# PSU_2x.net
KiCad netlist of a schematic drawn in EAGLE
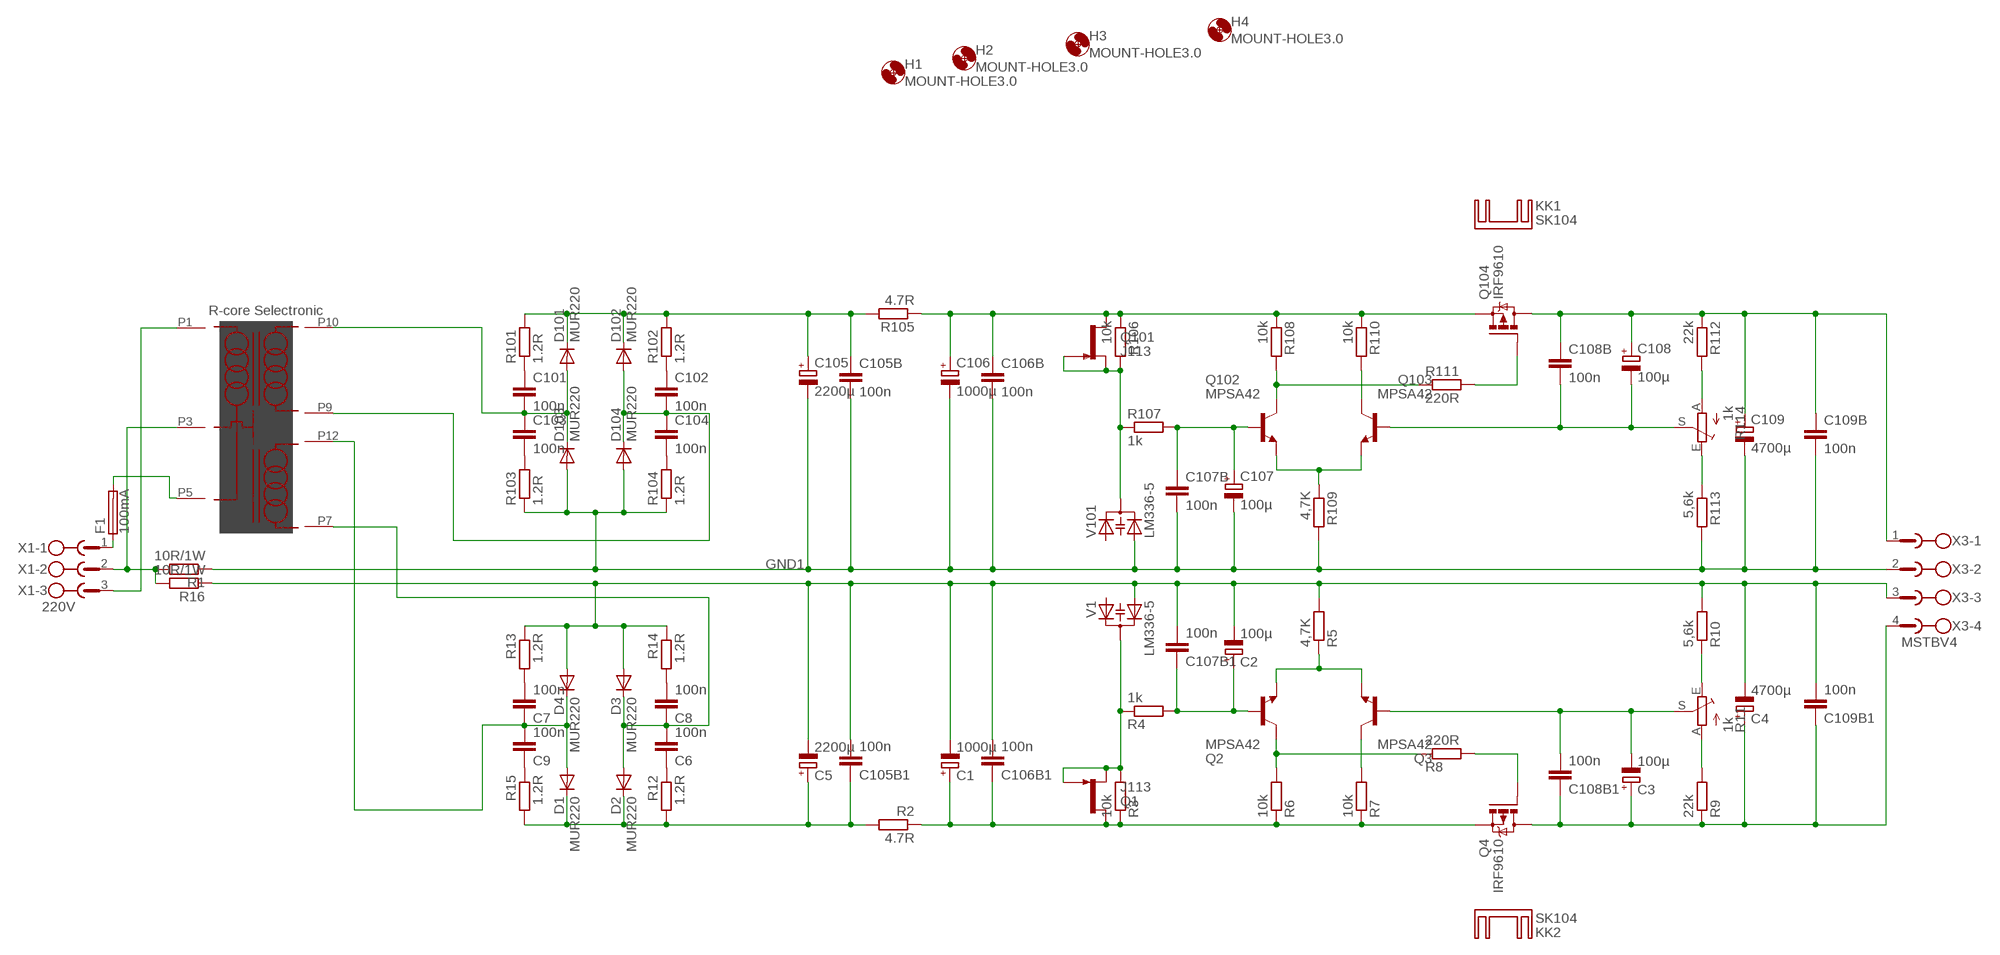
[diagram p0: schematic, sheet 1]

(export (version "E")
  (design (tool "Eeschema 10.0.6"))
  (components
    (comp (ref "C1")
      (value "1000µ")
      (footprint "eagle-import:E7,5-16")
      (libsource (lib "eagle-import") (part "CPOL-EUE7.5-16"))
    )
    (comp (ref "C2")
      (value "100µ")
      (footprint "eagle-import:E5-10,5")
      (libsource (lib "eagle-import") (part "CPOL-EUE5-10.5"))
    )
    (comp (ref "C3")
      (value "100µ")
      (footprint "eagle-import:E5-10,5")
      (libsource (lib "eagle-import") (part "CPOL-EUE5-10.5"))
    )
    (comp (ref "C4")
      (value "4700µ")
      (footprint "eagle-import:EB25D")
      (libsource (lib "eagle-import") (part "CPOL-EUE10-25"))
    )
    (comp (ref "C5")
      (value "2200µ")
      (footprint "eagle-import:E7,5-16")
      (libsource (lib "eagle-import") (part "CPOL-EUE7.5-16"))
    )
    (comp (ref "C6")
      (value "100n")
      (footprint "eagle-import:C050-025X075")
      (libsource (lib "eagle-import") (part "C-EU050-025X075"))
    )
    (comp (ref "C7")
      (value "100n")
      (footprint "eagle-import:C050-025X075")
      (libsource (lib "eagle-import") (part "C-EU050-025X075"))
    )
    (comp (ref "C8")
      (value "100n")
      (footprint "eagle-import:C050-025X075")
      (libsource (lib "eagle-import") (part "C-EU050-025X075"))
    )
    (comp (ref "C9")
      (value "100n")
      (footprint "eagle-import:C050-025X075")
      (libsource (lib "eagle-import") (part "C-EU050-025X075"))
    )
    (comp (ref "C101")
      (value "100n")
      (footprint "eagle-import:C050-025X075")
      (libsource (lib "eagle-import") (part "C-EU050-025X075"))
    )
    (comp (ref "C102")
      (value "100n")
      (footprint "eagle-import:C050-025X075")
      (libsource (lib "eagle-import") (part "C-EU050-025X075"))
    )
    (comp (ref "C103")
      (value "100n")
      (footprint "eagle-import:C050-025X075")
      (libsource (lib "eagle-import") (part "C-EU050-025X075"))
    )
    (comp (ref "C104")
      (value "100n")
      (footprint "eagle-import:C050-025X075")
      (libsource (lib "eagle-import") (part "C-EU050-025X075"))
    )
    (comp (ref "C105")
      (value "2200µ")
      (footprint "eagle-import:E7,5-16")
      (libsource (lib "eagle-import") (part "CPOL-EUE7.5-16"))
    )
    (comp (ref "C105B")
      (value "100n")
      (footprint "eagle-import:C050-025X075")
      (libsource (lib "eagle-import") (part "C-EU050-025X075"))
    )
    (comp (ref "C105B1")
      (value "100n")
      (footprint "eagle-import:C050-025X075")
      (libsource (lib "eagle-import") (part "C-EU050-025X075"))
    )
    (comp (ref "C106")
      (value "1000µ")
      (footprint "eagle-import:E7,5-16")
      (libsource (lib "eagle-import") (part "CPOL-EUE7.5-16"))
    )
    (comp (ref "C106B")
      (value "100n")
      (footprint "eagle-import:C050-025X075")
      (libsource (lib "eagle-import") (part "C-EU050-025X075"))
    )
    (comp (ref "C106B1")
      (value "100n")
      (footprint "eagle-import:C050-025X075")
      (libsource (lib "eagle-import") (part "C-EU050-025X075"))
    )
    (comp (ref "C107")
      (value "100µ")
      (footprint "eagle-import:E5-10,5")
      (libsource (lib "eagle-import") (part "CPOL-EUE5-10.5"))
    )
    (comp (ref "C107B")
      (value "100n")
      (footprint "eagle-import:C050-025X075")
      (libsource (lib "eagle-import") (part "C-EU050-025X075"))
    )
    (comp (ref "C107B1")
      (value "100n")
      (footprint "eagle-import:C050-025X075")
      (libsource (lib "eagle-import") (part "C-EU050-025X075"))
    )
    (comp (ref "C108")
      (value "100µ")
      (footprint "eagle-import:E5-10,5")
      (libsource (lib "eagle-import") (part "CPOL-EUE5-10.5"))
    )
    (comp (ref "C108B")
      (value "100n")
      (footprint "eagle-import:C050-025X075")
      (libsource (lib "eagle-import") (part "C-EU050-025X075"))
    )
    (comp (ref "C108B1")
      (value "100n")
      (footprint "eagle-import:C050-025X075")
      (libsource (lib "eagle-import") (part "C-EU050-025X075"))
    )
    (comp (ref "C109")
      (value "4700µ")
      (footprint "eagle-import:EB25D")
      (libsource (lib "eagle-import") (part "CPOL-EUE10-25"))
    )
    (comp (ref "C109B")
      (value "100n")
      (footprint "eagle-import:C050-025X075")
      (libsource (lib "eagle-import") (part "C-EU050-025X075"))
    )
    (comp (ref "C109B1")
      (value "100n")
      (footprint "eagle-import:C050-025X075")
      (libsource (lib "eagle-import") (part "C-EU050-025X075"))
    )
    (comp (ref "D1")
      (value "MUR220")
      (footprint "eagle-import:DO201-15")
      (libsource (lib "eagle-import") (part "BY500"))
    )
    (comp (ref "D2")
      (value "MUR220")
      (footprint "eagle-import:DO201-15")
      (libsource (lib "eagle-import") (part "BY500"))
    )
    (comp (ref "D3")
      (value "MUR220")
      (footprint "eagle-import:DO201-15")
      (libsource (lib "eagle-import") (part "BY500"))
    )
    (comp (ref "D4")
      (value "MUR220")
      (footprint "eagle-import:DO201-15")
      (libsource (lib "eagle-import") (part "BY500"))
    )
    (comp (ref "D101")
      (value "MUR220")
      (footprint "eagle-import:DO201-15")
      (libsource (lib "eagle-import") (part "BY500"))
    )
    (comp (ref "D102")
      (value "MUR220")
      (footprint "eagle-import:DO201-15")
      (libsource (lib "eagle-import") (part "BY500"))
    )
    (comp (ref "D103")
      (value "MUR220")
      (footprint "eagle-import:DO201-15")
      (libsource (lib "eagle-import") (part "BY500"))
    )
    (comp (ref "D104")
      (value "MUR220")
      (footprint "eagle-import:DO201-15")
      (libsource (lib "eagle-import") (part "BY500"))
    )
    (comp (ref "F1")
      (value "100mA")
      (footprint "eagle-import:GSH15")
      (fields (field (name "MPN") "64900001039"))
      (libsource (lib "eagle-import") (part "GSH15"))
    )
    (comp (ref "H1")
      (value "MOUNT-HOLE3.0")
      (footprint "eagle-import:3,0")
      (libsource (lib "eagle-import") (part "MOUNT-HOLE3.0"))
    )
    (comp (ref "H2")
      (value "MOUNT-HOLE3.0")
      (footprint "eagle-import:3,0")
      (libsource (lib "eagle-import") (part "MOUNT-HOLE3.0"))
    )
    (comp (ref "H3")
      (value "MOUNT-HOLE3.0")
      (footprint "eagle-import:3,0")
      (libsource (lib "eagle-import") (part "MOUNT-HOLE3.0"))
    )
    (comp (ref "H4")
      (value "MOUNT-HOLE3.0")
      (footprint "eagle-import:3,0")
      (libsource (lib "eagle-import") (part "MOUNT-HOLE3.0"))
    )
    (comp (ref "KK1")
      (value "SK104")
      (footprint "eagle-import:SK104")
      (libsource (lib "eagle-import") (part "SK104"))
    )
    (comp (ref "KK2")
      (value "SK104")
      (footprint "eagle-import:SK104")
      (libsource (lib "eagle-import") (part "SK104"))
    )
    (comp (ref "Q1")
      (value "J113")
      (footprint "eagle-import:TO-92")
      (libsource (lib "eagle-import") (part "2N5458"))
    )
    (comp (ref "Q2")
      (value "MPSA42")
      (footprint "eagle-import:TO92-EBC")
      (libsource (lib "eagle-import") (part "-NPN-TO92-EBC"))
    )
    (comp (ref "Q3")
      (value "MPSA42")
      (footprint "eagle-import:TO92-EBC")
      (libsource (lib "eagle-import") (part "-NPN-TO92-EBC"))
    )
    (comp (ref "Q4")
      (value "IRF9610")
      (footprint "eagle-import:TO220BV")
      (libsource (lib "eagle-import") (part "IRF9530"))
    )
    (comp (ref "Q101")
      (value "J113")
      (footprint "eagle-import:TO-92")
      (libsource (lib "eagle-import") (part "2N5458"))
    )
    (comp (ref "Q102")
      (value "MPSA42")
      (footprint "eagle-import:TO92-EBC")
      (libsource (lib "eagle-import") (part "-NPN-TO92-EBC"))
    )
    (comp (ref "Q103")
      (value "MPSA42")
      (footprint "eagle-import:TO92-EBC")
      (libsource (lib "eagle-import") (part "-NPN-TO92-EBC"))
    )
    (comp (ref "Q104")
      (value "IRF9610")
      (footprint "eagle-import:TO220BV")
      (libsource (lib "eagle-import") (part "IRF9530"))
    )
    (comp (ref "R1")
      (value "10R/1W")
      (footprint "eagle-import:0309_12")
      (libsource (lib "eagle-import") (part "R-EU_0309/12"))
    )
    (comp (ref "R2")
      (value "4.7R")
      (footprint "eagle-import:0207_10")
      (libsource (lib "eagle-import") (part "R-EU_0207/10"))
    )
    (comp (ref "R3")
      (value "10k")
      (footprint "eagle-import:0207_10")
      (libsource (lib "eagle-import") (part "R-EU_0207/10"))
    )
    (comp (ref "R4")
      (value "1k")
      (footprint "eagle-import:0207_10")
      (libsource (lib "eagle-import") (part "R-EU_0207/10"))
    )
    (comp (ref "R5")
      (value "4,7K")
      (footprint "eagle-import:0207_10")
      (libsource (lib "eagle-import") (part "R-EU_0207/10"))
    )
    (comp (ref "R6")
      (value "10k")
      (footprint "eagle-import:0207_10")
      (libsource (lib "eagle-import") (part "R-EU_0207/10"))
    )
    (comp (ref "R7")
      (value "10k")
      (footprint "eagle-import:0207_10")
      (libsource (lib "eagle-import") (part "R-EU_0207/10"))
    )
    (comp (ref "R8")
      (value "220R")
      (footprint "eagle-import:0207_10")
      (libsource (lib "eagle-import") (part "R-EU_0207/10"))
    )
    (comp (ref "R9")
      (value "22k")
      (footprint "eagle-import:0207_10")
      (libsource (lib "eagle-import") (part "R-EU_0207/10"))
    )
    (comp (ref "R10")
      (value "5,6k")
      (footprint "eagle-import:0207_10")
      (libsource (lib "eagle-import") (part "R-EU_0207/10"))
    )
    (comp (ref "R11")
      (value "1k")
      (footprint "eagle-import:S64W")
      (libsource (lib "eagle-import") (part "TRIM_EU-S64W"))
    )
    (comp (ref "R12")
      (value "1.2R")
      (footprint "eagle-import:0207_10")
      (libsource (lib "eagle-import") (part "R-EU_0207/10"))
    )
    (comp (ref "R13")
      (value "1.2R")
      (footprint "eagle-import:0207_10")
      (libsource (lib "eagle-import") (part "R-EU_0207/10"))
    )
    (comp (ref "R14")
      (value "1.2R")
      (footprint "eagle-import:0207_10")
      (libsource (lib "eagle-import") (part "R-EU_0207/10"))
    )
    (comp (ref "R15")
      (value "1.2R")
      (footprint "eagle-import:0207_10")
      (libsource (lib "eagle-import") (part "R-EU_0207/10"))
    )
    (comp (ref "R16")
      (value "10R/1W")
      (footprint "eagle-import:0309_12")
      (libsource (lib "eagle-import") (part "R-EU_0309/12"))
    )
    (comp (ref "R101")
      (value "1.2R")
      (footprint "eagle-import:0207_10")
      (libsource (lib "eagle-import") (part "R-EU_0207/10"))
    )
    (comp (ref "R102")
      (value "1.2R")
      (footprint "eagle-import:0207_10")
      (libsource (lib "eagle-import") (part "R-EU_0207/10"))
    )
    (comp (ref "R103")
      (value "1.2R")
      (footprint "eagle-import:0207_10")
      (libsource (lib "eagle-import") (part "R-EU_0207/10"))
    )
    (comp (ref "R104")
      (value "1.2R")
      (footprint "eagle-import:0207_10")
      (libsource (lib "eagle-import") (part "R-EU_0207/10"))
    )
    (comp (ref "R105")
      (value "4.7R")
      (footprint "eagle-import:0207_10")
      (libsource (lib "eagle-import") (part "R-EU_0207/10"))
    )
    (comp (ref "R106")
      (value "10k")
      (footprint "eagle-import:0207_10")
      (libsource (lib "eagle-import") (part "R-EU_0207/10"))
    )
    (comp (ref "R107")
      (value "1k")
      (footprint "eagle-import:0207_10")
      (libsource (lib "eagle-import") (part "R-EU_0207/10"))
    )
    (comp (ref "R108")
      (value "10k")
      (footprint "eagle-import:0207_10")
      (libsource (lib "eagle-import") (part "R-EU_0207/10"))
    )
    (comp (ref "R109")
      (value "4,7K")
      (footprint "eagle-import:0207_10")
      (libsource (lib "eagle-import") (part "R-EU_0207/10"))
    )
    (comp (ref "R110")
      (value "10k")
      (footprint "eagle-import:0207_10")
      (libsource (lib "eagle-import") (part "R-EU_0207/10"))
    )
    (comp (ref "R111")
      (value "220R")
      (footprint "eagle-import:0207_10")
      (libsource (lib "eagle-import") (part "R-EU_0207/10"))
    )
    (comp (ref "R112")
      (value "22k")
      (footprint "eagle-import:0207_10")
      (libsource (lib "eagle-import") (part "R-EU_0207/10"))
    )
    (comp (ref "R113")
      (value "5,6k")
      (footprint "eagle-import:0207_10")
      (libsource (lib "eagle-import") (part "R-EU_0207/10"))
    )
    (comp (ref "R114")
      (value "1k")
      (footprint "eagle-import:S64W")
      (libsource (lib "eagle-import") (part "TRIM_EU-S64W"))
    )
    (comp (ref "U$1")
      (value "R-CORE-SELECTRONIC-PCB")
      (footprint "eagle-import:R-CORE48MM")
      (libsource (lib "eagle-import") (part "R-CORE-SELECTRONIC-PCB"))
    )
    (comp (ref "V1")
      (value "LM336-5")
      (footprint "eagle-import:SOT54E")
      (libsource (lib "eagle-import") (part "DIODE-2CAPACITANCESOT54E"))
    )
    (comp (ref "V101")
      (value "LM336-5")
      (footprint "eagle-import:SOT54E")
      (libsource (lib "eagle-import") (part "DIODE-2CAPACITANCESOT54E"))
    )
    (comp (ref "X1")
      (value "220V")
      (footprint "eagle-import:MSTBV3")
      (fields (field (name "MPN") "MSTBV 2,5/3-GF-5.08"))
      (libsource (lib "eagle-import") (part "MSTBV3"))
    )
    (comp (ref "X3")
      (value "MSTBV4")
      (footprint "eagle-import:MSTBV4")
      (fields (field (name "MPN") "MSTBV 2,5/4-GF-5.08"))
      (libsource (lib "eagle-import") (part "MSTBV4"))
    )
  )
  (nets
    (net (code "1") (name "/GND1") (class "Default")
      (node (ref "C105") (pin "-") (pinfunction "-_-") (pintype "passive"))
      (node (ref "C105B") (pin "2") (pinfunction "2_2") (pintype "passive"))
      (node (ref "C106") (pin "-") (pinfunction "-_-") (pintype "passive"))
      (node (ref "C106B") (pin "2") (pinfunction "2_2") (pintype "passive"))
      (node (ref "C107") (pin "-") (pinfunction "-_-") (pintype "passive"))
      (node (ref "C107B") (pin "2") (pinfunction "2_2") (pintype "passive"))
      (node (ref "C109") (pin "-") (pinfunction "-_-") (pintype "passive"))
      (node (ref "C109B") (pin "2") (pinfunction "2_2") (pintype "passive"))
      (node (ref "D103") (pin "A") (pinfunction "A_A") (pintype "passive"))
      (node (ref "D104") (pin "A") (pinfunction "A_A") (pintype "passive"))
      (node (ref "R1") (pin "1") (pinfunction "1_1") (pintype "passive"))
      (node (ref "R103") (pin "1") (pinfunction "1_1") (pintype "passive"))
      (node (ref "R104") (pin "1") (pinfunction "1_1") (pintype "passive"))
      (node (ref "R109") (pin "2") (pinfunction "2_2") (pintype "passive"))
      (node (ref "R113") (pin "2") (pinfunction "2_2") (pintype "passive"))
      (node (ref "V101") (pin "A2") (pinfunction "A2_A2") (pintype "passive"))
      (node (ref "X3") (pin "2") (pinfunction "1_2") (pintype "passive"))
    )
    (net (code "2") (name "Net-(C6-Pad1)") (class "Default")
      (node (ref "C6") (pin "1") (pinfunction "1_1") (pintype "passive"))
      (node (ref "R12") (pin "1") (pinfunction "1_1") (pintype "passive"))
    )
    (net (code "3") (name "Net-(C7-Pad2)") (class "Default")
      (node (ref "C7") (pin "2") (pinfunction "2_2") (pintype "passive"))
      (node (ref "R13") (pin "2") (pinfunction "2_2") (pintype "passive"))
    )
    (net (code "4") (name "Net-(C8-Pad2)") (class "Default")
      (node (ref "C8") (pin "2") (pinfunction "2_2") (pintype "passive"))
      (node (ref "R14") (pin "2") (pinfunction "2_2") (pintype "passive"))
    )
    (net (code "5") (name "Net-(C9-Pad1)") (class "Default")
      (node (ref "C9") (pin "1") (pinfunction "1_1") (pintype "passive"))
      (node (ref "R15") (pin "1") (pinfunction "1_1") (pintype "passive"))
    )
    (net (code "6") (name "Net-(C101-Pad1)") (class "Default")
      (node (ref "C101") (pin "1") (pinfunction "1_1") (pintype "passive"))
      (node (ref "R101") (pin "1") (pinfunction "1_1") (pintype "passive"))
    )
    (net (code "7") (name "Net-(C102-Pad1)") (class "Default")
      (node (ref "C102") (pin "1") (pinfunction "1_1") (pintype "passive"))
      (node (ref "R102") (pin "1") (pinfunction "1_1") (pintype "passive"))
    )
    (net (code "8") (name "Net-(C103-Pad2)") (class "Default")
      (node (ref "C103") (pin "2") (pinfunction "2_2") (pintype "passive"))
      (node (ref "R103") (pin "2") (pinfunction "2_2") (pintype "passive"))
    )
    (net (code "9") (name "Net-(C104-Pad2)") (class "Default")
      (node (ref "C104") (pin "2") (pinfunction "2_2") (pintype "passive"))
      (node (ref "R104") (pin "2") (pinfunction "2_2") (pintype "passive"))
    )
    (net (code "10") (name "Net-(C105-Pad+)") (class "Default")
      (node (ref "C105") (pin "+") (pinfunction "+_+") (pintype "passive"))
      (node (ref "C105B") (pin "1") (pinfunction "1_1") (pintype "passive"))
      (node (ref "D101") (pin "C") (pinfunction "C_C") (pintype "passive"))
      (node (ref "D102") (pin "C") (pinfunction "C_C") (pintype "passive"))
      (node (ref "R101") (pin "2") (pinfunction "2_2") (pintype "passive"))
      (node (ref "R102") (pin "2") (pinfunction "2_2") (pintype "passive"))
      (node (ref "R105") (pin "2") (pinfunction "2_2") (pintype "passive"))
    )
    (net (code "11") (name "Net-(C105B1-Pad1)") (class "Default")
      (node (ref "C105B1") (pin "1") (pinfunction "1_1") (pintype "passive"))
      (node (ref "C5") (pin "+") (pinfunction "+_+") (pintype "passive"))
      (node (ref "D1") (pin "C") (pinfunction "C_C") (pintype "passive"))
      (node (ref "D2") (pin "C") (pinfunction "C_C") (pintype "passive"))
      (node (ref "R12") (pin "2") (pinfunction "2_2") (pintype "passive"))
      (node (ref "R15") (pin "2") (pinfunction "2_2") (pintype "passive"))
      (node (ref "R2") (pin "2") (pinfunction "2_2") (pintype "passive"))
    )
    (net (code "12") (name "Net-(C107-Pad+)") (class "Default")
      (node (ref "C107") (pin "+") (pinfunction "+_+") (pintype "passive"))
      (node (ref "C107B") (pin "1") (pinfunction "1_1") (pintype "passive"))
      (node (ref "Q102") (pin "B") (pinfunction "B_B") (pintype "passive"))
      (node (ref "R107") (pin "2") (pinfunction "2_2") (pintype "passive"))
    )
    (net (code "13") (name "Net-(C107B1-Pad1)") (class "Default")
      (node (ref "C107B1") (pin "1") (pinfunction "1_1") (pintype "passive"))
      (node (ref "C2") (pin "+") (pinfunction "+_+") (pintype "passive"))
      (node (ref "Q2") (pin "B") (pinfunction "B_B") (pintype "passive"))
      (node (ref "R4") (pin "2") (pinfunction "2_2") (pintype "passive"))
    )
    (net (code "14") (name "Net-(C108-Pad+)") (class "Default")
      (node (ref "C108") (pin "+") (pinfunction "+_+") (pintype "passive"))
      (node (ref "C108B") (pin "1") (pinfunction "1_1") (pintype "passive"))
      (node (ref "C109") (pin "+") (pinfunction "+_+") (pintype "passive"))
      (node (ref "C109B") (pin "1") (pinfunction "1_1") (pintype "passive"))
      (node (ref "Q104") (pin "D") (pinfunction "D_D") (pintype "passive"))
      (node (ref "R112") (pin "1") (pinfunction "1_1") (pintype "passive"))
      (node (ref "X3") (pin "1") (pinfunction "1_1") (pintype "passive"))
    )
    (net (code "15") (name "Net-(C108-Pad-)") (class "Default")
      (node (ref "C108") (pin "-") (pinfunction "-_-") (pintype "passive"))
      (node (ref "C108B") (pin "2") (pinfunction "2_2") (pintype "passive"))
      (node (ref "Q103") (pin "B") (pinfunction "B_B") (pintype "passive"))
      (node (ref "R114") (pin "S") (pinfunction "S_S") (pintype "passive"))
    )
    (net (code "16") (name "Net-(C108B1-Pad2)") (class "Default")
      (node (ref "C108B1") (pin "2") (pinfunction "2_2") (pintype "passive"))
      (node (ref "C3") (pin "-") (pinfunction "-_-") (pintype "passive"))
      (node (ref "Q3") (pin "B") (pinfunction "B_B") (pintype "passive"))
      (node (ref "R11") (pin "S") (pinfunction "S_S") (pintype "passive"))
    )
    (net (code "17") (name "Net-(F1-Pad1)") (class "Default")
      (node (ref "F1") (pin "1") (pinfunction "1_1") (pintype "passive"))
      (node (ref "X1") (pin "1") (pinfunction "1_1") (pintype "passive"))
    )
    (net (code "18") (name "Net-(Q1-D)") (class "Default")
      (node (ref "C1") (pin "+") (pinfunction "+_+") (pintype "passive"))
      (node (ref "C106B1") (pin "1") (pinfunction "1_1") (pintype "passive"))
      (node (ref "Q1") (pin "1") (pinfunction "D_1") (pintype "passive"))
      (node (ref "Q4") (pin "S") (pinfunction "S_S") (pintype "passive"))
      (node (ref "R2") (pin "1") (pinfunction "1_1") (pintype "passive"))
      (node (ref "R3") (pin "1") (pinfunction "1_1") (pintype "passive"))
      (node (ref "R6") (pin "1") (pinfunction "1_1") (pintype "passive"))
      (node (ref "R7") (pin "1") (pinfunction "1_1") (pintype "passive"))
    )
    (net (code "19") (name "Net-(Q1-G)") (class "Default")
      (node (ref "Q1") (pin "2") (pinfunction "S_2") (pintype "passive"))
      (node (ref "Q1") (pin "3") (pinfunction "G_3") (pintype "passive"))
      (node (ref "R3") (pin "2") (pinfunction "2_2") (pintype "passive"))
      (node (ref "R4") (pin "1") (pinfunction "1_1") (pintype "passive"))
      (node (ref "V1") (pin "C") (pinfunction "C_C") (pintype "passive"))
    )
    (net (code "20") (name "Net-(Q2-PadC)") (class "Default")
      (node (ref "Q2") (pin "C") (pinfunction "C_C") (pintype "passive"))
      (node (ref "R6") (pin "2") (pinfunction "2_2") (pintype "passive"))
      (node (ref "R8") (pin "1") (pinfunction "1_1") (pintype "passive"))
    )
    (net (code "21") (name "Net-(Q2-PadE)") (class "Default")
      (node (ref "Q2") (pin "E") (pinfunction "E_E") (pintype "passive"))
      (node (ref "Q3") (pin "E") (pinfunction "E_E") (pintype "passive"))
      (node (ref "R5") (pin "1") (pinfunction "1_1") (pintype "passive"))
    )
    (net (code "22") (name "Net-(Q3-PadC)") (class "Default")
      (node (ref "Q3") (pin "C") (pinfunction "C_C") (pintype "passive"))
      (node (ref "R7") (pin "2") (pinfunction "2_2") (pintype "passive"))
    )
    (net (code "23") (name "Net-(Q4-PadG)") (class "Default")
      (node (ref "Q4") (pin "G") (pinfunction "G_G") (pintype "passive"))
      (node (ref "R8") (pin "2") (pinfunction "2_2") (pintype "passive"))
    )
    (net (code "24") (name "Net-(Q101-D)") (class "Default")
      (node (ref "C106") (pin "+") (pinfunction "+_+") (pintype "passive"))
      (node (ref "C106B") (pin "1") (pinfunction "1_1") (pintype "passive"))
      (node (ref "Q101") (pin "1") (pinfunction "D_1") (pintype "passive"))
      (node (ref "Q104") (pin "S") (pinfunction "S_S") (pintype "passive"))
      (node (ref "R105") (pin "1") (pinfunction "1_1") (pintype "passive"))
      (node (ref "R106") (pin "1") (pinfunction "1_1") (pintype "passive"))
      (node (ref "R108") (pin "1") (pinfunction "1_1") (pintype "passive"))
      (node (ref "R110") (pin "1") (pinfunction "1_1") (pintype "passive"))
    )
    (net (code "25") (name "Net-(Q101-G)") (class "Default")
      (node (ref "Q101") (pin "2") (pinfunction "S_2") (pintype "passive"))
      (node (ref "Q101") (pin "3") (pinfunction "G_3") (pintype "passive"))
      (node (ref "R106") (pin "2") (pinfunction "2_2") (pintype "passive"))
      (node (ref "R107") (pin "1") (pinfunction "1_1") (pintype "passive"))
      (node (ref "V101") (pin "C") (pinfunction "C_C") (pintype "passive"))
    )
    (net (code "26") (name "Net-(Q102-PadC)") (class "Default")
      (node (ref "Q102") (pin "C") (pinfunction "C_C") (pintype "passive"))
      (node (ref "R108") (pin "2") (pinfunction "2_2") (pintype "passive"))
      (node (ref "R111") (pin "1") (pinfunction "1_1") (pintype "passive"))
    )
    (net (code "27") (name "Net-(Q102-PadE)") (class "Default")
      (node (ref "Q102") (pin "E") (pinfunction "E_E") (pintype "passive"))
      (node (ref "Q103") (pin "E") (pinfunction "E_E") (pintype "passive"))
      (node (ref "R109") (pin "1") (pinfunction "1_1") (pintype "passive"))
    )
    (net (code "28") (name "Net-(Q103-PadC)") (class "Default")
      (node (ref "Q103") (pin "C") (pinfunction "C_C") (pintype "passive"))
      (node (ref "R110") (pin "2") (pinfunction "2_2") (pintype "passive"))
    )
    (net (code "29") (name "Net-(Q104-PadG)") (class "Default")
      (node (ref "Q104") (pin "G") (pinfunction "G_G") (pintype "passive"))
      (node (ref "R111") (pin "2") (pinfunction "2_2") (pintype "passive"))
    )
    (net (code "30") (name "Net-(R10-Pad1)") (class "Default")
      (node (ref "R10") (pin "1") (pinfunction "1_1") (pintype "passive"))
      (node (ref "R11") (pin "E") (pinfunction "E_E") (pintype "passive"))
    )
    (net (code "31") (name "Net-(R11-PadA)") (class "Default")
      (node (ref "R11") (pin "A") (pinfunction "A_A") (pintype "passive"))
      (node (ref "R9") (pin "2") (pinfunction "2_2") (pintype "passive"))
    )
    (net (code "32") (name "Net-(R112-Pad2)") (class "Default")
      (node (ref "R112") (pin "2") (pinfunction "2_2") (pintype "passive"))
      (node (ref "R114") (pin "A") (pinfunction "A_A") (pintype "passive"))
    )
    (net (code "33") (name "Net-(R113-Pad1)") (class "Default")
      (node (ref "R113") (pin "1") (pinfunction "1_1") (pintype "passive"))
      (node (ref "R114") (pin "E") (pinfunction "E_E") (pintype "passive"))
    )
    (net (code "34") (name "Net-(U$1-PRIM-1)") (class "Default")
      (node (ref "U$1") (pin "P1") (pinfunction "PRIM-1_P1") (pintype "bidirectional"))
      (node (ref "X1") (pin "3") (pinfunction "1_3") (pintype "passive"))
    )
    (net (code "35") (name "Net-(U$1-PRIM5)") (class "Default")
      (node (ref "F1") (pin "2") (pinfunction "2_2") (pintype "passive"))
      (node (ref "U$1") (pin "P5") (pinfunction "PRIM5_P5") (pintype "bidirectional"))
    )
    (net (code "36") (name "Net-(U$1-SEC1-7)") (class "Default")
      (node (ref "C6") (pin "2") (pinfunction "2_2") (pintype "passive"))
      (node (ref "C8") (pin "1") (pinfunction "1_1") (pintype "passive"))
      (node (ref "D2") (pin "A") (pinfunction "A_A") (pintype "passive"))
      (node (ref "D3") (pin "C") (pinfunction "C_C") (pintype "passive"))
      (node (ref "U$1") (pin "P7") (pinfunction "SEC1-7_P7") (pintype "bidirectional"))
    )
    (net (code "37") (name "Net-(U$1-SEC1-12)") (class "Default")
      (node (ref "C7") (pin "1") (pinfunction "1_1") (pintype "passive"))
      (node (ref "C9") (pin "2") (pinfunction "2_2") (pintype "passive"))
      (node (ref "D1") (pin "A") (pinfunction "A_A") (pintype "passive"))
      (node (ref "D4") (pin "C") (pinfunction "C_C") (pintype "passive"))
      (node (ref "U$1") (pin "P12") (pinfunction "SEC1-12_P12") (pintype "bidirectional"))
    )
    (net (code "38") (name "Net-(U$1-SEC2-9)") (class "Default")
      (node (ref "C102") (pin "2") (pinfunction "2_2") (pintype "passive"))
      (node (ref "C104") (pin "1") (pinfunction "1_1") (pintype "passive"))
      (node (ref "D102") (pin "A") (pinfunction "A_A") (pintype "passive"))
      (node (ref "D104") (pin "C") (pinfunction "C_C") (pintype "passive"))
      (node (ref "U$1") (pin "P9") (pinfunction "SEC2-9_P9") (pintype "bidirectional"))
    )
    (net (code "39") (name "Net-(U$1-SEC2-10)") (class "Default")
      (node (ref "C101") (pin "2") (pinfunction "2_2") (pintype "passive"))
      (node (ref "C103") (pin "1") (pinfunction "1_1") (pintype "passive"))
      (node (ref "D101") (pin "A") (pinfunction "A_A") (pintype "passive"))
      (node (ref "D103") (pin "C") (pinfunction "C_C") (pintype "passive"))
      (node (ref "U$1") (pin "P10") (pinfunction "SEC2-10_P10") (pintype "bidirectional"))
    )
    (net (code "40") (name "Net-(U$1-SHIELD3)") (class "Default")
      (node (ref "R1") (pin "2") (pinfunction "2_2") (pintype "passive"))
      (node (ref "R16") (pin "2") (pinfunction "2_2") (pintype "passive"))
      (node (ref "U$1") (pin "P3") (pinfunction "SHIELD3_P3") (pintype "bidirectional"))
      (node (ref "X1") (pin "2") (pinfunction "1_2") (pintype "passive"))
    )
    (net (code "41") (name "Net-(X3C-1)") (class "Default")
      (node (ref "C1") (pin "-") (pinfunction "-_-") (pintype "passive"))
      (node (ref "C105B1") (pin "2") (pinfunction "2_2") (pintype "passive"))
      (node (ref "C106B1") (pin "2") (pinfunction "2_2") (pintype "passive"))
      (node (ref "C107B1") (pin "2") (pinfunction "2_2") (pintype "passive"))
      (node (ref "C109B1") (pin "2") (pinfunction "2_2") (pintype "passive"))
      (node (ref "C2") (pin "-") (pinfunction "-_-") (pintype "passive"))
      (node (ref "C4") (pin "-") (pinfunction "-_-") (pintype "passive"))
      (node (ref "C5") (pin "-") (pinfunction "-_-") (pintype "passive"))
      (node (ref "D3") (pin "A") (pinfunction "A_A") (pintype "passive"))
      (node (ref "D4") (pin "A") (pinfunction "A_A") (pintype "passive"))
      (node (ref "R10") (pin "2") (pinfunction "2_2") (pintype "passive"))
      (node (ref "R13") (pin "1") (pinfunction "1_1") (pintype "passive"))
      (node (ref "R14") (pin "1") (pinfunction "1_1") (pintype "passive"))
      (node (ref "R16") (pin "1") (pinfunction "1_1") (pintype "passive"))
      (node (ref "R5") (pin "2") (pinfunction "2_2") (pintype "passive"))
      (node (ref "V1") (pin "A2") (pinfunction "A2_A2") (pintype "passive"))
      (node (ref "X3") (pin "3") (pinfunction "1_3") (pintype "passive"))
    )
    (net (code "42") (name "Net-(X3D-1)") (class "Default")
      (node (ref "C108B1") (pin "1") (pinfunction "1_1") (pintype "passive"))
      (node (ref "C109B1") (pin "1") (pinfunction "1_1") (pintype "passive"))
      (node (ref "C3") (pin "+") (pinfunction "+_+") (pintype "passive"))
      (node (ref "C4") (pin "+") (pinfunction "+_+") (pintype "passive"))
      (node (ref "Q4") (pin "D") (pinfunction "D_D") (pintype "passive"))
      (node (ref "R9") (pin "1") (pinfunction "1_1") (pintype "passive"))
      (node (ref "X3") (pin "4") (pinfunction "1_4") (pintype "passive"))
    )
    (net (code "43") (name "unconnected-(V1-PadA1)") (class "Default")
      (node (ref "V1") (pin "A1") (pinfunction "A1_A1") (pintype "passive"))
    )
    (net (code "44") (name "unconnected-(V101-PadA1)") (class "Default")
      (node (ref "V101") (pin "A1") (pinfunction "A1_A1") (pintype "passive"))
    )
  )
)
